# AMS_Sheet1.net
KiCad netlist of a schematic drawn in Altium Designer
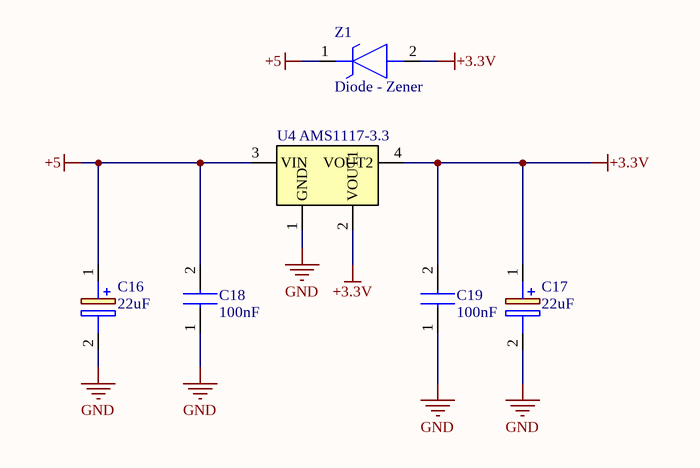
[diagram p0: AMS_Sheet1.SchDoc]

(export (version "E")
  (design (tool "Eeschema 10.0.6"))
  (components
    (comp (ref "C16")
      (value "22uF")
      (footprint "CAPP_Lytic_D_6.6")
      (description "Capacitor Polarised")
      (libsource (lib "Faydali_Yuk_Schlib1") (part "Cap - Pol"))
    )
    (comp (ref "C17")
      (value "22uF")
      (footprint "CAPP_Lytic_D_6.6")
      (description "Capacitor Polarised")
      (libsource (lib "Faydali_Yuk_Schlib1") (part "Cap - Pol"))
    )
    (comp (ref "C18")
      (value "100nF")
      (footprint "CAP - 0603")
      (description "Capacitor")
      (libsource (lib "Faydali_Yuk_Schlib1") (part "CAP"))
    )
    (comp (ref "C19")
      (value "100nF")
      (footprint "CAP - 0603")
      (description "Capacitor")
      (libsource (lib "Faydali_Yuk_Schlib1") (part "CAP"))
    )
    (comp (ref "U4")
      (value "AMS1117-3.3")
      (footprint "SOT-223 - AMS1117-3.3")
      (libsource (lib "Faydali_Yuk_Schlib1") (part "AMS1117-3.3"))
    )
    (comp (ref "Z1")
      (value "Diode - Zener")
      (footprint "SOD-80 (MINIMELF)")
      (description "Zener Diode")
      (libsource (lib "Faydali_Yuk_Schlib1") (part "Diode - Zener"))
    )
  )
  (nets
    (net (code "1") (name "+3.3V") (class "Default")
      (node (ref "C17") (pin "1") (pinfunction "+_1") (pintype "passive"))
      (node (ref "C19") (pin "2") (pinfunction "2_2") (pintype "passive"))
      (node (ref "U4") (pin "2") (pinfunction "VOUT1_2") (pintype "passive"))
      (node (ref "U4") (pin "4") (pinfunction "VOUT2_4") (pintype "passive"))
      (node (ref "Z1") (pin "2") (pinfunction "A_2") (pintype "passive"))
    )
    (net (code "2") (name "+5") (class "Default")
      (node (ref "C16") (pin "1") (pinfunction "+_1") (pintype "passive"))
      (node (ref "C18") (pin "2") (pinfunction "2_2") (pintype "passive"))
      (node (ref "U4") (pin "3") (pinfunction "VIN_3") (pintype "passive"))
      (node (ref "Z1") (pin "1") (pinfunction "K_1") (pintype "passive"))
    )
    (net (code "3") (name "GND") (class "Default")
      (node (ref "C16") (pin "2") (pinfunction "-_2") (pintype "passive"))
      (node (ref "C17") (pin "2") (pinfunction "-_2") (pintype "passive"))
      (node (ref "C18") (pin "1") (pinfunction "1_1") (pintype "passive"))
      (node (ref "C19") (pin "1") (pinfunction "1_1") (pintype "passive"))
      (node (ref "U4") (pin "1") (pinfunction "GND_1") (pintype "passive"))
    )
  )
)
